# Raspberry_HAT.net
KiCad netlist of a schematic drawn in Altium Designer
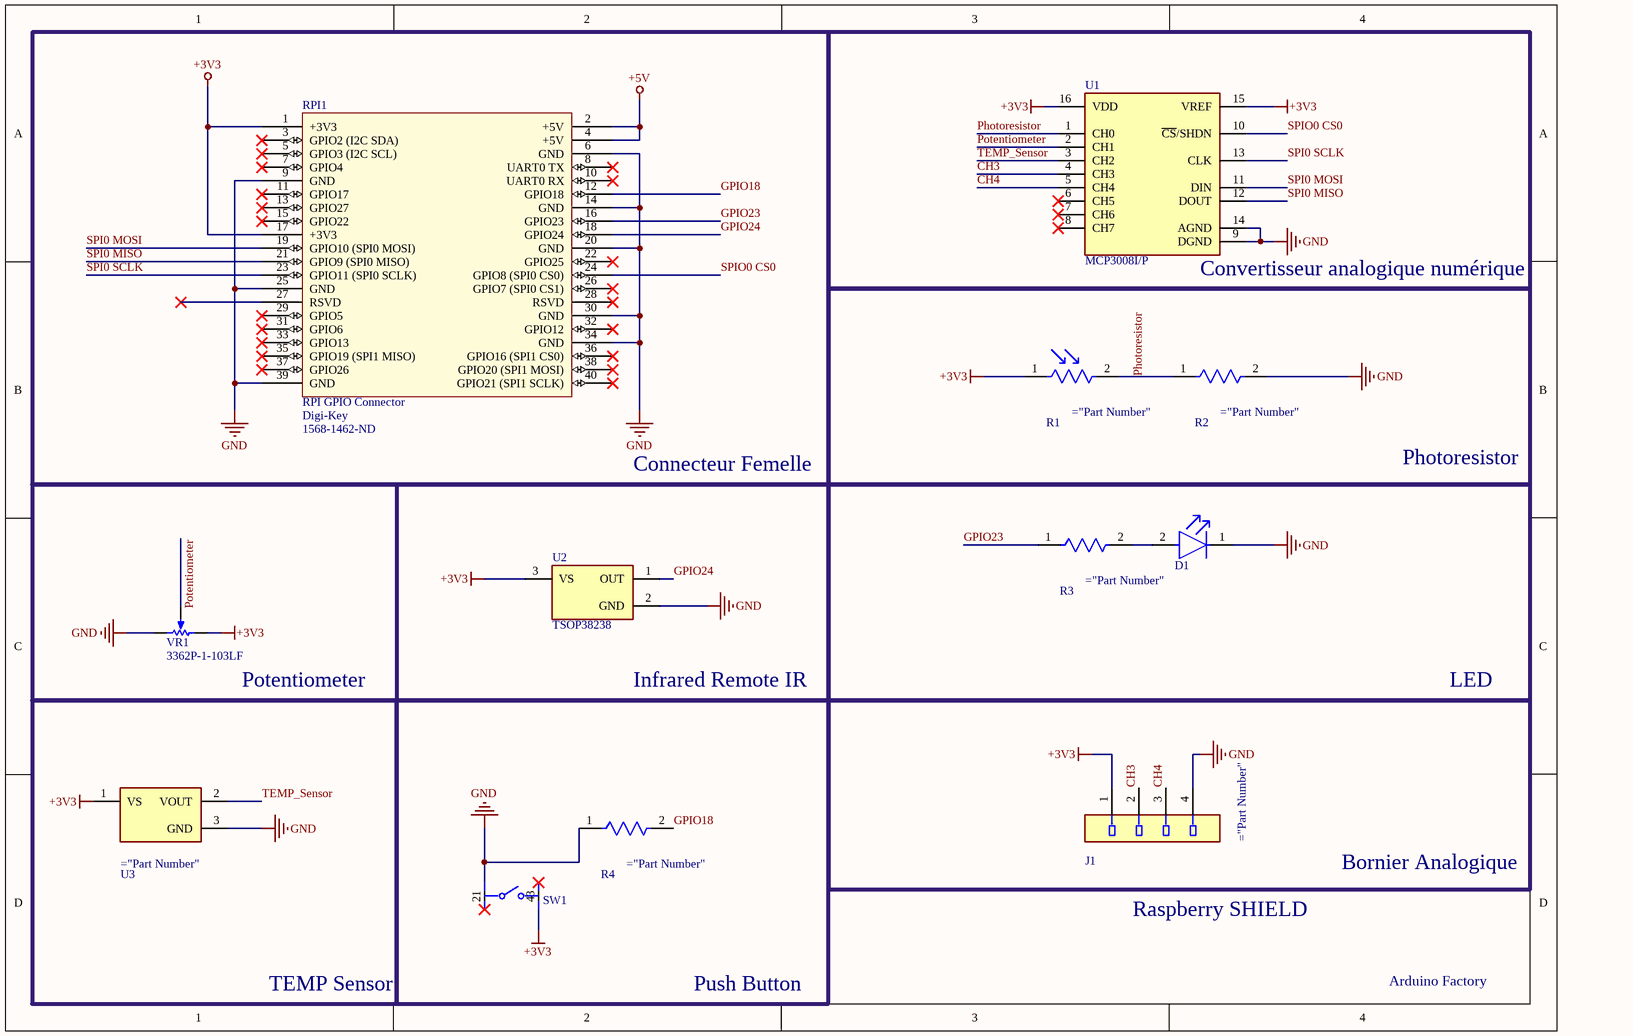
[diagram p0: Raspberry_HAT.SchDoc]

(export (version "E")
  (design (tool "Eeschema 10.0.6"))
  (components
    (comp (ref "D1")
      (value "Diode_Vishay_TLDR4900_eec")
      (footprint "Vishay_TLDR4900_0")
      (description "DIODE Red 648nm LED Indication - Discrete 1.8V Radial")
      (fields (field (name "PART NUMBER") "TLDR4900") (field (name "MANUFACTURER") "Vishay"))
      (libsource (lib "Diode_Vishay_TLDR4900_eec") (part "Diode_Vishay_TLDR4900_eec"))
    )
    (comp (ref "J1")
      (value "61300411121")
      (footprint "Wurth_61300511121_0")
      (libsource (lib "Conn_Wurth_61300411121_eec") (part "61300411121"))
    )
    (comp (ref "R1")
      (value "PDV-P9002")
      (footprint "Advanced_Photonix_PDV-P9002_0")
      (libsource (lib "Res_Advanced_Photonix_PDV-P9002_eec") (part "PDV-P9002"))
    )
    (comp (ref "R2")
      (value "CF14JT10K0")
      (footprint "Stackpole_Electronics_Inc._CF14JT1K00_0")
      (libsource (lib "Res_Stackpole_CF14JT10K0_eec") (part "CF14JT10K0"))
    )
    (comp (ref "R3")
      (value "CF14JT10K0")
      (footprint "Stackpole_Electronics_Inc._CF14JT1K00_0")
      (libsource (lib "Res_Stackpole_CF14JT10K0_eec") (part "CF14JT10K0"))
    )
    (comp (ref "R4")
      (value "CF14JT10K0")
      (footprint "Stackpole_Electronics_Inc._CF14JT1K00_0")
      (libsource (lib "Res_Stackpole_CF14JT10K0_eec") (part "CF14JT10K0"))
    )
    (comp (ref "RPI1")
      (value "RPI GPIO Connector")
      (footprint "rpi")
      (description "GPIO Header for Raspberry Pi A+/B+/Pi 2/Pi 3 - 2x20")
      (fields
        (field (name "MANUFACTURER") "SparkFun Electronics")
        (field (name "MANUFACTURER PART NUMBER") "PRT-14017")
        (field (name "SUPPLIER 1") "Digi-Key")
        (field (name "SUPPLIER PART NUMBER 1") "1568-1462-ND")
      )
      (libsource (lib "rpi") (part "rpi connector"))
    )
    (comp (ref "SW1")
      (value "Switch_TE_FSM4JH_eec")
      (footprint "TE_FSM4JH_0")
      (description "SWITCH TACTILE SPST-NO 0.05A 24V")
      (fields (field (name "PART NUMBER") "FSM4JH") (field (name "VOLTAGE") "12"))
      (libsource (lib "Switch_TE_FSM4JH_eec") (part "Switch_TE_FSM4JH_eec"))
    )
    (comp (ref "U1")
      (value "IC_Microchip_MCP3008I-P_eec")
      (footprint "Microchip_MCP3008I-P_0")
      (description "IC ADC 10BIT 2.7V 8CH SPI 16DIP")
      (fields
        (field (name "PART NUMBER") "MCP3008I/P")
        (field (name "MANUFACTURER") "Microchip")
        (field (name "MOUSER PART NUMBER") "579-MCP3008-I/P")
      )
      (libsource (lib "IC_Microchip_MCP3008I-P_eec") (part "IC_Microchip_MCP3008I-P_eec"))
    )
    (comp (ref "U2")
      (value "IC_Vishay_TSOP38238_eec")
      (footprint "Vishay_TSOP38238_0")
      (description "IC IR RCVR MOD 38KHZ DOME RADIAL")
      (fields
        (field (name "PART NUMBER") "TSOP38238")
        (field (name "MANUFACTURER") "Vishay")
        (field (name "MOUSER PART NUMBER") "782-TSOP38238")
      )
      (libsource (lib "IC_Vishay_TSOP38238_eec") (part "IC_Vishay_TSOP38238_eec"))
    )
    (comp (ref "U3")
      (value "TMP36GT9Z")
      (footprint "Vishay_TSOP38238_0")
      (libsource (lib "IC_Analog_Devices_TMP36GT9Z_eec") (part "TMP36GT9Z"))
    )
    (comp (ref "VR1")
      (value "3362P-1-103LF")
      (footprint "BOUR-3362P")
      (description "Square Trimpot(R) Trimming Potentiometer, 10 KOhm, 300 V, -55 to 125 degC, 3-Pin THD, RoHS, Tube")
      (fields (field (name "TOLERANCE") "1%"))
      (libsource (lib "Bourns_3362P_1_103LF") (part "3362P-1-103LF"))
    )
  )
  (nets
    (net (code "1") (name "+3V3") (class "Default")
      (node (ref "J1") (pin "1") (pinfunction "1_1") (pintype "passive"))
      (node (ref "R1") (pin "1") (pinfunction "1_1") (pintype "passive"))
      (node (ref "RPI1") (pin "1") (pinfunction "+3V3_1") (pintype "power_in"))
      (node (ref "RPI1") (pin "17") (pinfunction "+3V3_17") (pintype "power_in"))
      (node (ref "SW1") (pin "4") (pinfunction "4_4") (pintype "passive"))
      (node (ref "U1") (pin "15") (pinfunction "VREF_15") (pintype "passive"))
      (node (ref "U1") (pin "16") (pinfunction "VDD_16") (pintype "passive"))
      (node (ref "U2") (pin "3") (pinfunction "VS_3") (pintype "passive"))
      (node (ref "U3") (pin "1") (pinfunction "VS_1") (pintype "passive"))
      (node (ref "VR1") (pin "1") (pinfunction "CCW_1") (pintype "passive"))
    )
    (net (code "2") (name "+5V") (class "Default")
      (node (ref "RPI1") (pin "2") (pinfunction "+5V_2") (pintype "power_in"))
      (node (ref "RPI1") (pin "4") (pinfunction "+5V_4") (pintype "power_in"))
    )
    (net (code "3") (name "/CH3") (class "Default")
      (node (ref "J1") (pin "2") (pinfunction "2_2") (pintype "passive"))
      (node (ref "U1") (pin "4") (pinfunction "CH3_4") (pintype "passive"))
    )
    (net (code "4") (name "/CH4") (class "Default")
      (node (ref "J1") (pin "3") (pinfunction "3_3") (pintype "passive"))
      (node (ref "U1") (pin "5") (pinfunction "CH4_5") (pintype "passive"))
    )
    (net (code "5") (name "/GPIO18") (class "Default")
      (node (ref "R4") (pin "2") (pinfunction "2_2") (pintype "passive"))
      (node (ref "RPI1") (pin "12") (pinfunction "GPIO18_12") (pintype "bidirectional"))
    )
    (net (code "6") (name "/GPIO23") (class "Default")
      (node (ref "R3") (pin "1") (pinfunction "1_1") (pintype "passive"))
      (node (ref "RPI1") (pin "16") (pinfunction "GPIO23_16") (pintype "bidirectional"))
    )
    (net (code "7") (name "/GPIO24") (class "Default")
      (node (ref "RPI1") (pin "18") (pinfunction "GPIO24_18") (pintype "bidirectional"))
      (node (ref "U2") (pin "1") (pinfunction "OUT_1") (pintype "passive"))
    )
    (net (code "8") (name "/Photoresistor") (class "Default")
      (node (ref "R1") (pin "2") (pinfunction "2_2") (pintype "passive"))
      (node (ref "R2") (pin "1") (pinfunction "1_1") (pintype "passive"))
      (node (ref "U1") (pin "1") (pinfunction "CH0_1") (pintype "passive"))
    )
    (net (code "9") (name "/Potentiometer") (class "Default")
      (node (ref "U1") (pin "2") (pinfunction "CH1_2") (pintype "passive"))
      (node (ref "VR1") (pin "2") (pinfunction "S_2") (pintype "passive"))
    )
    (net (code "10") (name "/SPI0 MISO") (class "Default")
      (node (ref "RPI1") (pin "21") (pinfunction "GPIO9_(SPI0_MISO)_21") (pintype "bidirectional"))
      (node (ref "U1") (pin "12") (pinfunction "DOUT_12") (pintype "passive"))
    )
    (net (code "11") (name "/SPI0 MOSI") (class "Default")
      (node (ref "RPI1") (pin "19") (pinfunction "GPIO10_(SPI0_MOSI)_19") (pintype "bidirectional"))
      (node (ref "U1") (pin "11") (pinfunction "DIN_11") (pintype "passive"))
    )
    (net (code "12") (name "/SPI0 SCLK") (class "Default")
      (node (ref "RPI1") (pin "23") (pinfunction "GPIO11_(SPI0_SCLK)_23") (pintype "bidirectional"))
      (node (ref "U1") (pin "13") (pinfunction "CLK_13") (pintype "passive"))
    )
    (net (code "13") (name "/SPIO0 CS0") (class "Default")
      (node (ref "RPI1") (pin "24") (pinfunction "GPIO8_(SPI0_CS0)_24") (pintype "bidirectional"))
      (node (ref "U1") (pin "10") (pinfunction "~{CS}/SHDN_10") (pintype "passive"))
    )
    (net (code "14") (name "/TEMP_Sensor") (class "Default")
      (node (ref "U1") (pin "3") (pinfunction "CH2_3") (pintype "passive"))
      (node (ref "U3") (pin "2") (pinfunction "VOUT_2") (pintype "passive"))
    )
    (net (code "15") (name "GND") (class "Default")
      (node (ref "D1") (pin "1") (pinfunction "C_1") (pintype "passive"))
      (node (ref "J1") (pin "4") (pinfunction "4_4") (pintype "passive"))
      (node (ref "R2") (pin "2") (pinfunction "2_2") (pintype "passive"))
      (node (ref "R4") (pin "1") (pinfunction "1_1") (pintype "passive"))
      (node (ref "RPI1") (pin "14") (pinfunction "GND_14") (pintype "power_in"))
      (node (ref "RPI1") (pin "20") (pinfunction "GND_20") (pintype "power_in"))
      (node (ref "RPI1") (pin "25") (pinfunction "GND_25") (pintype "power_in"))
      (node (ref "RPI1") (pin "30") (pinfunction "GND_30") (pintype "power_in"))
      (node (ref "RPI1") (pin "34") (pinfunction "GND_34") (pintype "passive"))
      (node (ref "RPI1") (pin "39") (pinfunction "GND_39") (pintype "power_in"))
      (node (ref "RPI1") (pin "6") (pinfunction "GND_6") (pintype "power_in"))
      (node (ref "RPI1") (pin "9") (pinfunction "GND_9") (pintype "power_in"))
      (node (ref "SW1") (pin "1") (pinfunction "1_1") (pintype "passive"))
      (node (ref "U1") (pin "14") (pinfunction "AGND_14") (pintype "passive"))
      (node (ref "U1") (pin "9") (pinfunction "DGND_9") (pintype "passive"))
      (node (ref "U2") (pin "2") (pinfunction "GND_2") (pintype "passive"))
      (node (ref "U3") (pin "3") (pinfunction "GND_3") (pintype "passive"))
      (node (ref "VR1") (pin "3") (pinfunction "CW_3") (pintype "passive"))
    )
    (net (code "16") (name "Net-(D1-A)") (class "Default")
      (node (ref "D1") (pin "2") (pinfunction "A_2") (pintype "passive"))
      (node (ref "R3") (pin "2") (pinfunction "2_2") (pintype "passive"))
    )
    (net (code "17") (name "unconnected-(RPI1-GPIO2_(I2C_SDA)-Pad3)") (class "Default")
      (node (ref "RPI1") (pin "3") (pinfunction "GPIO2_(I2C_SDA)_3") (pintype "bidirectional+no_connect"))
    )
    (net (code "18") (name "unconnected-(RPI1-GPIO3_(I2C_SCL)-Pad5)") (class "Default")
      (node (ref "RPI1") (pin "5") (pinfunction "GPIO3_(I2C_SCL)_5") (pintype "bidirectional+no_connect"))
    )
    (net (code "19") (name "unconnected-(RPI1-GPIO4-Pad7)") (class "Default")
      (node (ref "RPI1") (pin "7") (pinfunction "GPIO4_7") (pintype "bidirectional+no_connect"))
    )
    (net (code "20") (name "unconnected-(RPI1-GPIO5-Pad29)") (class "Default")
      (node (ref "RPI1") (pin "29") (pinfunction "GPIO5_29") (pintype "bidirectional+no_connect"))
    )
    (net (code "21") (name "unconnected-(RPI1-GPIO6-Pad31)") (class "Default")
      (node (ref "RPI1") (pin "31") (pinfunction "GPIO6_31") (pintype "bidirectional+no_connect"))
    )
    (net (code "22") (name "unconnected-(RPI1-GPIO7_(SPI0_CS1)-Pad26)") (class "Default")
      (node (ref "RPI1") (pin "26") (pinfunction "GPIO7_(SPI0_CS1)_26") (pintype "bidirectional+no_connect"))
    )
    (net (code "23") (name "unconnected-(RPI1-GPIO12-Pad32)") (class "Default")
      (node (ref "RPI1") (pin "32") (pinfunction "GPIO12_32") (pintype "bidirectional+no_connect"))
    )
    (net (code "24") (name "unconnected-(RPI1-GPIO13-Pad33)") (class "Default")
      (node (ref "RPI1") (pin "33") (pinfunction "GPIO13_33") (pintype "bidirectional+no_connect"))
    )
    (net (code "25") (name "unconnected-(RPI1-GPIO16_(SPI1_CS0)-Pad36)") (class "Default")
      (node (ref "RPI1") (pin "36") (pinfunction "GPIO16_(SPI1_CS0)_36") (pintype "bidirectional+no_connect"))
    )
    (net (code "26") (name "unconnected-(RPI1-GPIO17-Pad11)") (class "Default")
      (node (ref "RPI1") (pin "11") (pinfunction "GPIO17_11") (pintype "bidirectional+no_connect"))
    )
    (net (code "27") (name "unconnected-(RPI1-GPIO19_(SPI1_MISO)-Pad35)") (class "Default")
      (node (ref "RPI1") (pin "35") (pinfunction "GPIO19_(SPI1_MISO)_35") (pintype "bidirectional+no_connect"))
    )
    (net (code "28") (name "unconnected-(RPI1-GPIO20_(SPI1_MOSI)-Pad38)") (class "Default")
      (node (ref "RPI1") (pin "38") (pinfunction "GPIO20_(SPI1_MOSI)_38") (pintype "bidirectional+no_connect"))
    )
    (net (code "29") (name "unconnected-(RPI1-GPIO21_(SPI1_SCLK)-Pad40)") (class "Default")
      (node (ref "RPI1") (pin "40") (pinfunction "GPIO21_(SPI1_SCLK)_40") (pintype "bidirectional+no_connect"))
    )
    (net (code "30") (name "unconnected-(RPI1-GPIO22-Pad15)") (class "Default")
      (node (ref "RPI1") (pin "15") (pinfunction "GPIO22_15") (pintype "bidirectional+no_connect"))
    )
    (net (code "31") (name "unconnected-(RPI1-GPIO25-Pad22)") (class "Default")
      (node (ref "RPI1") (pin "22") (pinfunction "GPIO25_22") (pintype "bidirectional+no_connect"))
    )
    (net (code "32") (name "unconnected-(RPI1-GPIO26-Pad37)") (class "Default")
      (node (ref "RPI1") (pin "37") (pinfunction "GPIO26_37") (pintype "bidirectional+no_connect"))
    )
    (net (code "33") (name "unconnected-(RPI1-GPIO27-Pad13)") (class "Default")
      (node (ref "RPI1") (pin "13") (pinfunction "GPIO27_13") (pintype "bidirectional+no_connect"))
    )
    (net (code "34") (name "unconnected-(RPI1-RSVD-Pad27)") (class "Default")
      (node (ref "RPI1") (pin "27") (pinfunction "RSVD_27") (pintype "passive+no_connect"))
    )
    (net (code "35") (name "unconnected-(RPI1-RSVD-Pad28)") (class "Default")
      (node (ref "RPI1") (pin "28") (pinfunction "RSVD_28") (pintype "passive+no_connect"))
    )
    (net (code "36") (name "unconnected-(RPI1-UART0_RX-Pad10)") (class "Default")
      (node (ref "RPI1") (pin "10") (pinfunction "UART0_RX_10") (pintype "bidirectional+no_connect"))
    )
    (net (code "37") (name "unconnected-(RPI1-UART0_TX-Pad8)") (class "Default")
      (node (ref "RPI1") (pin "8") (pinfunction "UART0_TX_8") (pintype "bidirectional+no_connect"))
    )
    (net (code "38") (name "unconnected-(SW1-Pad2)") (class "Default")
      (node (ref "SW1") (pin "2") (pinfunction "2_2") (pintype "passive+no_connect"))
    )
    (net (code "39") (name "unconnected-(SW1-Pad3)") (class "Default")
      (node (ref "SW1") (pin "3") (pinfunction "3_3") (pintype "passive+no_connect"))
    )
    (net (code "40") (name "unconnected-(U1-CH5-Pad6)") (class "Default")
      (node (ref "U1") (pin "6") (pinfunction "CH5_6") (pintype "passive+no_connect"))
    )
    (net (code "41") (name "unconnected-(U1-CH6-Pad7)") (class "Default")
      (node (ref "U1") (pin "7") (pinfunction "CH6_7") (pintype "passive+no_connect"))
    )
    (net (code "42") (name "unconnected-(U1-CH7-Pad8)") (class "Default")
      (node (ref "U1") (pin "8") (pinfunction "CH7_8") (pintype "passive+no_connect"))
    )
  )
)
